# Sheet3.net
KiCad netlist of a schematic drawn in Altium Designer
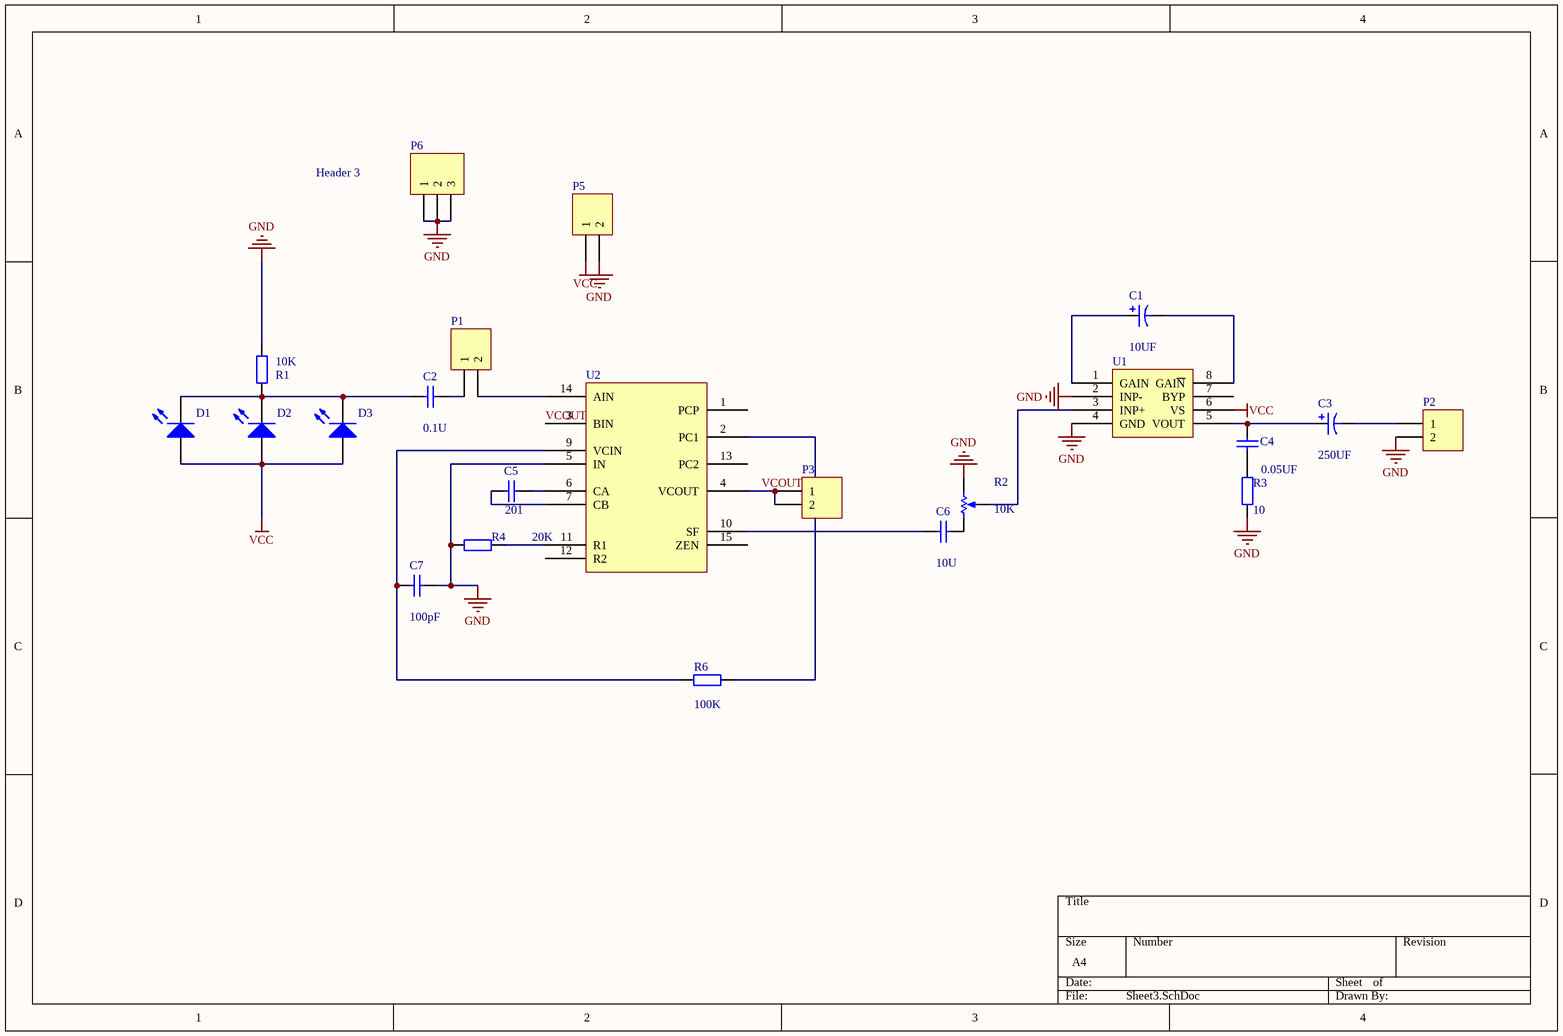
[diagram p0: Sheet3.SchDoc]

(export (version "E")
  (design (tool "Eeschema 10.0.6"))
  (components
    (comp (ref "C1")
      (value "10UF")
      (footprint "B")
      (description "Polarized Capacitor (Radial)")
      (fields (field (name "Comment") "Cap Pol1") (field (name "PUBLISHER") "Altium Limited"))
      (libsource (lib "Miscellaneous Devices") (part "Cap Pol1"))
    )
    (comp (ref "C2")
      (value "0.1U")
      (footprint "AXIAL-0.4")
      (description "Capacitor")
      (fields (field (name "Comment") "Cap") (field (name "PUBLISHER") "Altium Limited"))
      (libsource (lib "Miscellaneous Devices") (part "Cap"))
    )
    (comp (ref "C3")
      (value "250UF")
      (footprint "B")
      (description "Polarized Capacitor (Radial)")
      (fields (field (name "Comment") "Cap Pol1") (field (name "PUBLISHER") "Altium Limited"))
      (libsource (lib "Miscellaneous Devices") (part "Cap Pol1"))
    )
    (comp (ref "C4")
      (value "0.05UF")
      (footprint "6-0805")
      (description "Capacitor")
      (fields (field (name "Comment") "Cap") (field (name "PUBLISHER") "Altium Limited"))
      (libsource (lib "Miscellaneous Devices") (part "Cap"))
    )
    (comp (ref "C5")
      (value "201")
      (footprint "6-0805")
      (description "Capacitor")
      (fields (field (name "Comment") "Cap") (field (name "PUBLISHER") "Altium Limited"))
      (libsource (lib "Miscellaneous Devices") (part "Cap"))
    )
    (comp (ref "C6")
      (value "10U")
      (footprint "CAPPR5-5x5")
      (description "Capacitor")
      (fields (field (name "Comment") "Cap") (field (name "PUBLISHER") "Altium Limited"))
      (libsource (lib "Miscellaneous Devices") (part "Cap"))
    )
    (comp (ref "C7")
      (value "100pF")
      (footprint "CAPPR5-5x5")
      (description "Capacitor")
      (fields (field (name "Comment") "Cap") (field (name "PUBLISHER") "Altium Limited"))
      (libsource (lib "Miscellaneous Devices") (part "Cap"))
    )
    (comp (ref "D1")
      (value "LED0")
      (footprint "LED-0")
      (description "Typical INFRARED GaAs LED")
      (fields (field (name "PUBLISHER") "Altium Limited"))
      (libsource (lib "Miscellaneous Devices") (part "LED0"))
    )
    (comp (ref "D2")
      (value "LED0")
      (footprint "LED-0")
      (description "Typical INFRARED GaAs LED")
      (fields (field (name "PUBLISHER") "Altium Limited"))
      (libsource (lib "Miscellaneous Devices") (part "LED0"))
    )
    (comp (ref "D3")
      (value "LED0")
      (footprint "LED-0")
      (description "Typical INFRARED GaAs LED")
      (fields (field (name "PUBLISHER") "Altium Limited"))
      (libsource (lib "Miscellaneous Devices") (part "LED0"))
    )
    (comp (ref "P1")
      (value "Header 2")
      (footprint "HDR1X2")
      (description "Header, 2-Pin")
      (fields (field (name "PUBLISHER") "Altium Limited"))
      (libsource (lib "Miscellaneous Connectors") (part "Header 2"))
    )
    (comp (ref "P2")
      (value "Header 2")
      (footprint "HDR1X2")
      (description "Header, 2-Pin")
      (fields (field (name "PUBLISHER") "Altium Limited"))
      (libsource (lib "") (part "Header 2_1"))
    )
    (comp (ref "P3")
      (value "Header 2")
      (footprint "HDR1X2")
      (description "Header, 2-Pin")
      (fields (field (name "PUBLISHER") "Altium Limited"))
      (libsource (lib "") (part "Header 2_1"))
    )
    (comp (ref "P5")
      (value "Header 2")
      (footprint "HDR1X2")
      (description "Header, 2-Pin")
      (fields (field (name "PUBLISHER") "Altium Limited"))
      (libsource (lib "Miscellaneous Connectors") (part "Header 2"))
    )
    (comp (ref "P6")
      (value "Header 3")
      (footprint "HDR1X3")
      (description "Header, 3-Pin")
      (fields (field (name "PUBLISHER") "Altium Limited"))
      (libsource (lib "Miscellaneous Connectors") (part "Header 3"))
    )
    (comp (ref "R1")
      (value "10K")
      (footprint "6-0805")
      (description "Resistor")
      (fields (field (name "Comment") "Res2") (field (name "PUBLISHER") "Altium Limited"))
      (libsource (lib "Miscellaneous Devices") (part "Res2"))
    )
    (comp (ref "R2")
      (value "10K")
      (footprint "HDR1X3")
      (description "Potentiometer")
      (fields (field (name "PUBLISHER") "Altium Limited"))
      (libsource (lib "Miscellaneous Devices") (part "RPot"))
    )
    (comp (ref "R3")
      (value "10")
      (footprint "6-0805")
      (description "Resistor")
      (fields (field (name "Comment") "Res2") (field (name "PUBLISHER") "Altium Limited"))
      (libsource (lib "") (part "Res2_2"))
    )
    (comp (ref "R4")
      (value "20K")
      (footprint "6-0805")
      (description "Resistor")
      (fields (field (name "Comment") "Res2") (field (name "PUBLISHER") "Altium Limited"))
      (libsource (lib "") (part "Res2_1"))
    )
    (comp (ref "R6")
      (value "100K")
      (footprint "6-0805")
      (description "Resistor")
      (fields (field (name "Comment") "Res2") (field (name "PUBLISHER") "Altium Limited"))
      (libsource (lib "") (part "Res2_1"))
    )
    (comp (ref "U1") (value "LM386") (footprint "DIP-8") (libsource (lib "Schlib1") (part "LM386")))
    (comp (ref "U2") (value "CD4046") (footprint "DIP-16") (libsource (lib "Schlib1") (part "Component_1")))
  )
  (nets
    (net (code "1") (name "/VCOUT") (class "Default")
      (node (ref "P3") (pin "1") (pinfunction "1_1") (pintype "passive"))
      (node (ref "P3") (pin "2") (pinfunction "2_2") (pintype "passive"))
      (node (ref "U2") (pin "3") (pinfunction "BIN_3") (pintype "passive"))
      (node (ref "U2") (pin "4") (pinfunction "VCOUT_4") (pintype "passive"))
    )
    (net (code "2") (name "GND") (class "Default")
      (node (ref "C7") (pin "2") (pinfunction "2_2") (pintype "passive"))
      (node (ref "P2") (pin "2") (pinfunction "2_2") (pintype "passive"))
      (node (ref "P5") (pin "2") (pinfunction "2_2") (pintype "passive"))
      (node (ref "P6") (pin "1") (pinfunction "1_1") (pintype "passive"))
      (node (ref "P6") (pin "2") (pinfunction "2_2") (pintype "passive"))
      (node (ref "P6") (pin "3") (pinfunction "3_3") (pintype "passive"))
      (node (ref "R1") (pin "2") (pinfunction "2_2") (pintype "passive"))
      (node (ref "R2") (pin "3") (pinfunction "BOT_3") (pintype "passive"))
      (node (ref "R3") (pin "2") (pinfunction "2_2") (pintype "passive"))
      (node (ref "R4") (pin "2") (pinfunction "2_2") (pintype "passive"))
      (node (ref "U1") (pin "2") (pinfunction "INP-_2") (pintype "passive"))
      (node (ref "U1") (pin "4") (pinfunction "GND_4") (pintype "passive"))
      (node (ref "U2") (pin "5") (pinfunction "IN_5") (pintype "passive"))
    )
    (net (code "3") (name "Net-(C2-Pad2)") (class "Default")
      (node (ref "C2") (pin "2") (pinfunction "2_2") (pintype "passive"))
      (node (ref "P1") (pin "1") (pinfunction "1_1") (pintype "passive"))
    )
    (net (code "4") (name "Net-(C3-Pad2)") (class "Default")
      (node (ref "C3") (pin "2") (pinfunction "2_2") (pintype "passive"))
      (node (ref "P2") (pin "1") (pinfunction "1_1") (pintype "passive"))
    )
    (net (code "5") (name "Net-(C4-Pad1)") (class "Default")
      (node (ref "C4") (pin "1") (pinfunction "1_1") (pintype "passive"))
      (node (ref "R3") (pin "1") (pinfunction "1_1") (pintype "passive"))
    )
    (net (code "6") (name "Net-(D1-K)") (class "Default")
      (node (ref "C2") (pin "1") (pinfunction "1_1") (pintype "passive"))
      (node (ref "D1") (pin "2") (pinfunction "K_2") (pintype "passive"))
      (node (ref "D2") (pin "2") (pinfunction "K_2") (pintype "passive"))
      (node (ref "D3") (pin "2") (pinfunction "K_2") (pintype "passive"))
      (node (ref "R1") (pin "1") (pinfunction "1_1") (pintype "passive"))
    )
    (net (code "7") (name "Net-(R2-TAP)") (class "Default")
      (node (ref "R2") (pin "2") (pinfunction "TAP_2") (pintype "passive"))
      (node (ref "U1") (pin "3") (pinfunction "INP+_3") (pintype "passive"))
    )
    (net (code "8") (name "Net-(R2-TOP)") (class "Default")
      (node (ref "C6") (pin "2") (pinfunction "2_2") (pintype "passive"))
      (node (ref "R2") (pin "1") (pinfunction "TOP_1") (pintype "passive"))
    )
    (net (code "9") (name "Net-(U1-GAIN)") (class "Default")
      (node (ref "C1") (pin "1") (pinfunction "1_1") (pintype "passive"))
      (node (ref "U1") (pin "1") (pinfunction "GAIN_1") (pintype "passive"))
    )
    (net (code "10") (name "Net-(U1-GAI~{N})") (class "Default")
      (node (ref "C1") (pin "2") (pinfunction "2_2") (pintype "passive"))
      (node (ref "U1") (pin "8") (pinfunction "GAI~{N}_8") (pintype "passive"))
    )
    (net (code "11") (name "Net-(U1-VOUT)") (class "Default")
      (node (ref "C3") (pin "1") (pinfunction "1_1") (pintype "passive"))
      (node (ref "C4") (pin "2") (pinfunction "2_2") (pintype "passive"))
      (node (ref "U1") (pin "5") (pinfunction "VOUT_5") (pintype "passive"))
    )
    (net (code "12") (name "Net-(U2-AIN)") (class "Default")
      (node (ref "P1") (pin "2") (pinfunction "2_2") (pintype "passive"))
      (node (ref "U2") (pin "14") (pinfunction "AIN_14") (pintype "passive"))
    )
    (net (code "13") (name "Net-(U2-CA)") (class "Default")
      (node (ref "C5") (pin "2") (pinfunction "2_2") (pintype "passive"))
      (node (ref "U2") (pin "6") (pinfunction "CA_6") (pintype "passive"))
    )
    (net (code "14") (name "Net-(U2-CB)") (class "Default")
      (node (ref "C5") (pin "1") (pinfunction "1_1") (pintype "passive"))
      (node (ref "U2") (pin "7") (pinfunction "CB_7") (pintype "passive"))
    )
    (net (code "15") (name "Net-(U2-PC1)") (class "Default")
      (node (ref "R6") (pin "1") (pinfunction "1_1") (pintype "passive"))
      (node (ref "U2") (pin "2") (pinfunction "PC1_2") (pintype "passive"))
    )
    (net (code "16") (name "Net-(U2-R1)") (class "Default")
      (node (ref "R4") (pin "1") (pinfunction "1_1") (pintype "passive"))
      (node (ref "U2") (pin "11") (pinfunction "R1_11") (pintype "passive"))
    )
    (net (code "17") (name "Net-(U2-SF)") (class "Default")
      (node (ref "C6") (pin "1") (pinfunction "1_1") (pintype "passive"))
      (node (ref "U2") (pin "10") (pinfunction "SF_10") (pintype "passive"))
    )
    (net (code "18") (name "Net-(U2-VCIN)") (class "Default")
      (node (ref "C7") (pin "1") (pinfunction "1_1") (pintype "passive"))
      (node (ref "R6") (pin "2") (pinfunction "2_2") (pintype "passive"))
      (node (ref "U2") (pin "9") (pinfunction "VCIN_9") (pintype "passive"))
    )
    (net (code "19") (name "VCC") (class "Default")
      (node (ref "D1") (pin "1") (pinfunction "A_1") (pintype "passive"))
      (node (ref "D2") (pin "1") (pinfunction "A_1") (pintype "passive"))
      (node (ref "D3") (pin "1") (pinfunction "A_1") (pintype "passive"))
      (node (ref "P5") (pin "1") (pinfunction "1_1") (pintype "passive"))
      (node (ref "U1") (pin "6") (pinfunction "VS_6") (pintype "passive"))
    )
    (net (code "20") (name "unconnected-(U1-BYP-Pad7)") (class "Default")
      (node (ref "U1") (pin "7") (pinfunction "BYP_7") (pintype "passive"))
    )
    (net (code "21") (name "unconnected-(U2-PC2-Pad13)") (class "Default")
      (node (ref "U2") (pin "13") (pinfunction "PC2_13") (pintype "passive"))
    )
    (net (code "22") (name "unconnected-(U2-PCP-Pad1)") (class "Default")
      (node (ref "U2") (pin "1") (pinfunction "PCP_1") (pintype "passive"))
    )
    (net (code "23") (name "unconnected-(U2-R2-Pad12)") (class "Default")
      (node (ref "U2") (pin "12") (pinfunction "R2_12") (pintype "passive"))
    )
    (net (code "24") (name "unconnected-(U2-ZEN-Pad15)") (class "Default")
      (node (ref "U2") (pin "15") (pinfunction "ZEN_15") (pintype "passive"))
    )
  )
)
